# ccd700_trigger_in.net
KiCad netlist of a schematic drawn in EAGLE
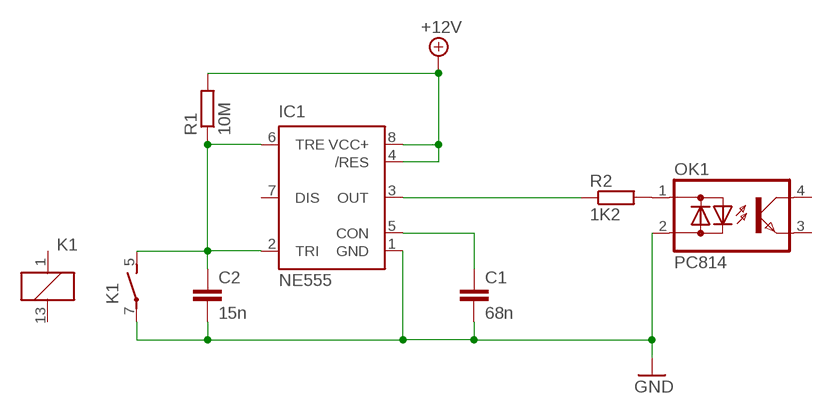
[diagram p0: schematic, sheet 1]

(export (version "E")
  (design (tool "Eeschema 10.0.6"))
  (components
    (comp (ref "C1")
      (value "68n")
      (footprint "eagle-import:C5B3")
      (libsource (lib "eagle-import") (part "C5/3"))
    )
    (comp (ref "C2")
      (value "15n")
      (footprint "eagle-import:C5B3")
      (libsource (lib "eagle-import") (part "C5/3"))
    )
    (comp (ref "IC1")
      (value "NE555")
      (footprint "eagle-import:DIL-08")
      (fields (field (name "MF") "Arrow Electronics") (field (name "MPN") "NE555N"))
      (libsource (lib "eagle-import") (part "NE555"))
    )
    (comp (ref "K1")
      (value "G6D-1A-ASI5VDC")
      (footprint "eagle-import:G6D")
      (libsource (lib "eagle-import") (part "G6D?-1A-ASI5VDC"))
    )
    (comp (ref "OK1")
      (value "PC814")
      (footprint "eagle-import:DIL04")
      (libsource (lib "eagle-import") (part "PC814"))
    )
    (comp (ref "R1")
      (value "10M")
      (footprint "eagle-import:0204_7")
      (libsource (lib "eagle-import") (part "R-EU_0204/7"))
    )
    (comp (ref "R2")
      (value "1K2")
      (footprint "eagle-import:0204_7")
      (libsource (lib "eagle-import") (part "R-EU_0204/7"))
    )
  )
  (nets
    (net (code "1") (name "+12V") (class "Default")
      (node (ref "IC1") (pin "4") (pinfunction "/RES_4") (pintype "input"))
      (node (ref "IC1") (pin "8") (pinfunction "VCC+_8") (pintype "power_in"))
      (node (ref "R1") (pin "2") (pinfunction "2_2") (pintype "passive"))
    )
    (net (code "2") (name "GND") (class "Default")
      (node (ref "C1") (pin "2") (pinfunction "2_2") (pintype "passive"))
      (node (ref "C2") (pin "2") (pinfunction "2_2") (pintype "passive"))
      (node (ref "IC1") (pin "1") (pinfunction "GND_1") (pintype "power_in"))
      (node (ref "K1") (pin "7") (pinfunction "P_7") (pintype "passive"))
      (node (ref "OK1") (pin "2") (pinfunction "AC2_2") (pintype "passive"))
    )
    (net (code "3") (name "Net-(IC1-CON)") (class "Default")
      (node (ref "C1") (pin "1") (pinfunction "1_1") (pintype "passive"))
      (node (ref "IC1") (pin "5") (pinfunction "CON_5") (pintype "input"))
    )
    (net (code "4") (name "Net-(IC1-OUT)") (class "Default")
      (node (ref "IC1") (pin "3") (pinfunction "OUT_3") (pintype "output"))
      (node (ref "R2") (pin "1") (pinfunction "1_1") (pintype "passive"))
    )
    (net (code "5") (name "Net-(IC1-TRE)") (class "Default")
      (node (ref "C2") (pin "1") (pinfunction "1_1") (pintype "passive"))
      (node (ref "IC1") (pin "2") (pinfunction "TRI_2") (pintype "input"))
      (node (ref "IC1") (pin "6") (pinfunction "TRE_6") (pintype "input"))
      (node (ref "K1") (pin "5") (pinfunction "S_5") (pintype "passive"))
      (node (ref "R1") (pin "1") (pinfunction "1_1") (pintype "passive"))
    )
    (net (code "6") (name "Net-(OK1-AC1)") (class "Default")
      (node (ref "OK1") (pin "1") (pinfunction "AC1_1") (pintype "passive"))
      (node (ref "R2") (pin "2") (pinfunction "2_2") (pintype "passive"))
    )
    (net (code "7") (name "unconnected-(IC1-DIS-Pad7)") (class "Default")
      (node (ref "IC1") (pin "7") (pinfunction "DIS_7") (pintype "input"))
    )
    (net (code "8") (name "unconnected-(K1-Pad1)") (class "Default")
      (node (ref "K1") (pin "1") (pinfunction "1_1") (pintype "passive"))
    )
    (net (code "9") (name "unconnected-(K1A-2-Pad13)") (class "Default")
      (node (ref "K1") (pin "13") (pinfunction "2_13") (pintype "passive"))
    )
    (net (code "10") (name "unconnected-(OK1-C-Pad4)") (class "Default")
      (node (ref "OK1") (pin "4") (pinfunction "C_4") (pintype "passive"))
    )
    (net (code "11") (name "unconnected-(OK1-E-Pad3)") (class "Default")
      (node (ref "OK1") (pin "3") (pinfunction "E_3") (pintype "passive"))
    )
  )
)
